# PLT-01-RevE.net
KiCad netlist of a schematic drawn in EAGLE
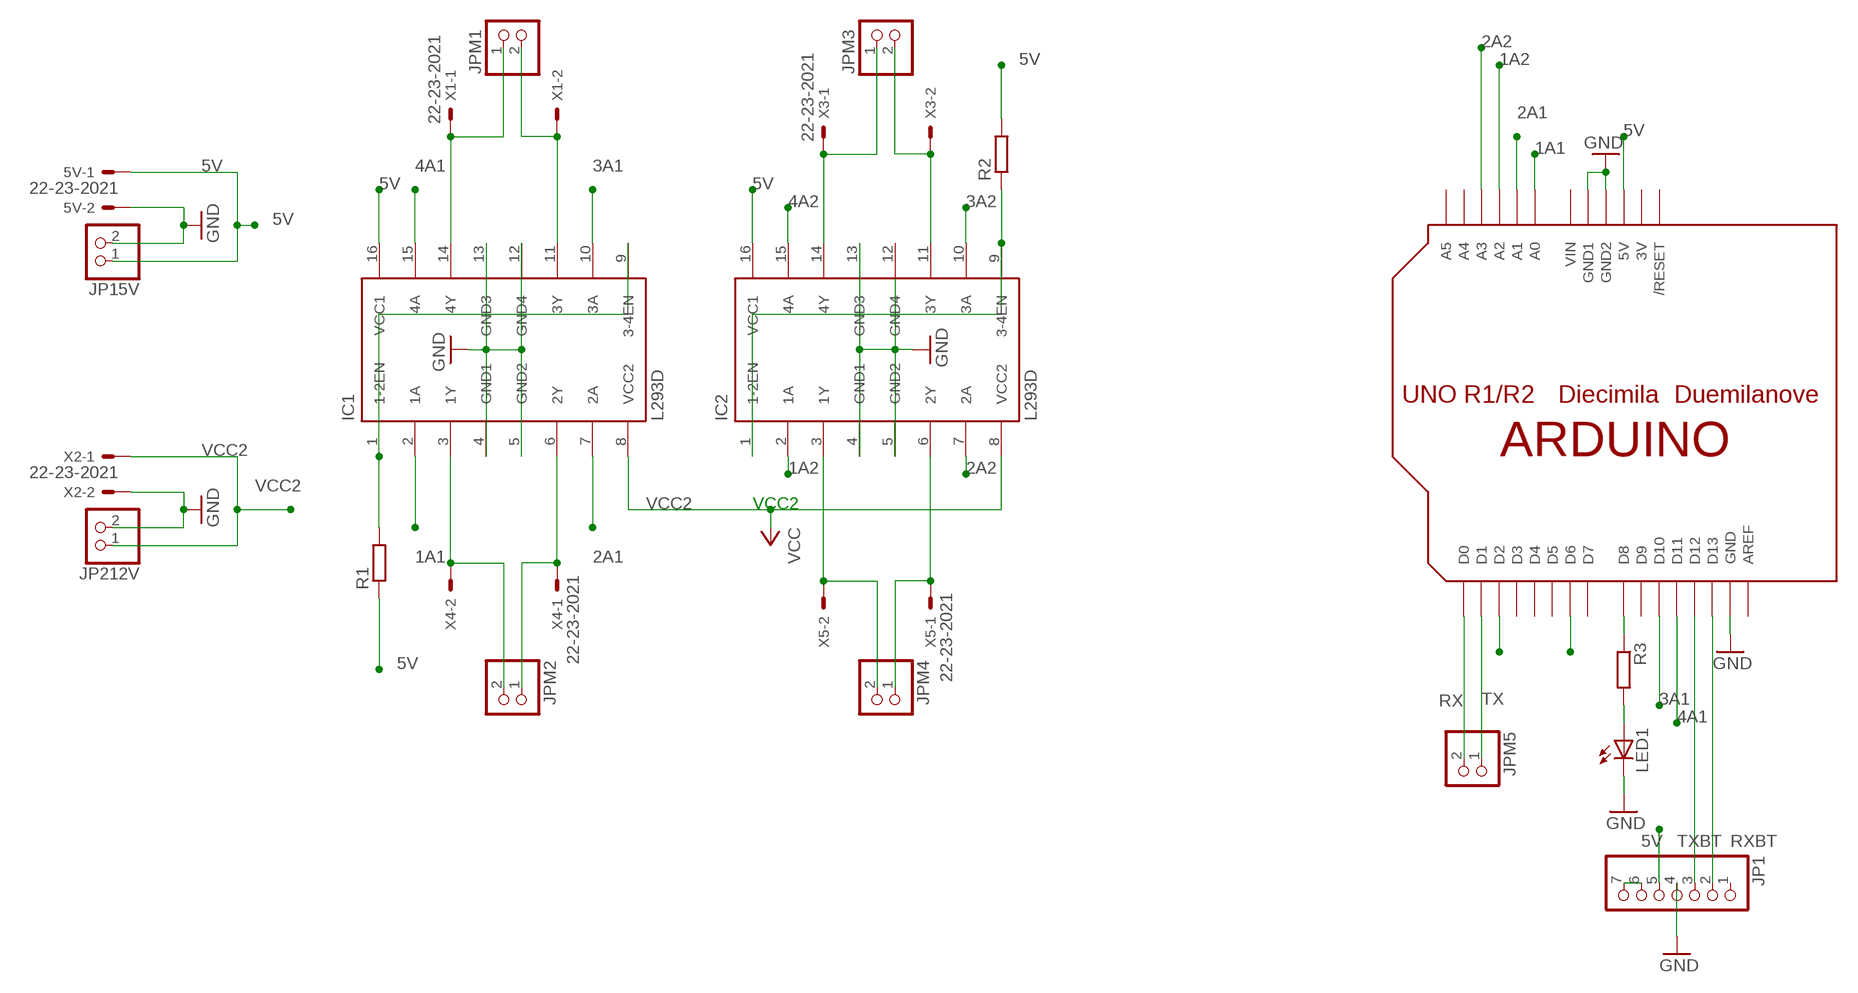
[diagram p0: schematic, sheet 1]

(export (version "E")
  (design (tool "Eeschema 10.0.6"))
  (components
    (comp (ref "5V")
      (value "22-23-2021")
      (footprint "eagle-import:22-23-2021")
      (fields (field (name "MF") "MOLEX"))
      (libsource (lib "eagle-import") (part "22-23-2021"))
    )
    (comp (ref "IC1")
      (value "L293D")
      (footprint "eagle-import:DIL16")
      (libsource (lib "eagle-import") (part "L293D"))
    )
    (comp (ref "IC2")
      (value "L293D")
      (footprint "eagle-import:DIL16")
      (libsource (lib "eagle-import") (part "L293D"))
    )
    (comp (ref "JP1")
      (value "PINHD-1X7")
      (footprint "eagle-import:1X07")
      (libsource (lib "eagle-import") (part "PINHD-1X7"))
    )
    (comp (ref "JP15V")
      (value "PINHD-1X2")
      (footprint "eagle-import:1X02")
      (libsource (lib "eagle-import") (part "PINHD-1X2"))
    )
    (comp (ref "JP212V")
      (value "PINHD-1X2")
      (footprint "eagle-import:1X02")
      (libsource (lib "eagle-import") (part "PINHD-1X2"))
    )
    (comp (ref "JPM1")
      (value "PINHD-1X2")
      (footprint "eagle-import:1X02")
      (libsource (lib "eagle-import") (part "PINHD-1X2"))
    )
    (comp (ref "JPM2")
      (value "PINHD-1X2")
      (footprint "eagle-import:1X02")
      (libsource (lib "eagle-import") (part "PINHD-1X2"))
    )
    (comp (ref "JPM3")
      (value "PINHD-1X2")
      (footprint "eagle-import:1X02")
      (libsource (lib "eagle-import") (part "PINHD-1X2"))
    )
    (comp (ref "JPM4")
      (value "PINHD-1X2")
      (footprint "eagle-import:1X02")
      (libsource (lib "eagle-import") (part "PINHD-1X2"))
    )
    (comp (ref "JPM5")
      (value "PINHD-1X2")
      (footprint "eagle-import:1X02")
      (libsource (lib "eagle-import") (part "PINHD-1X2"))
    )
    (comp (ref "LED1")
      (value "LED5MM")
      (footprint "eagle-import:LED5MM")
      (libsource (lib "eagle-import") (part "LED5MM"))
    )
    (comp (ref "R1")
      (value "R-EU_0207/10")
      (footprint "eagle-import:0207_10")
      (libsource (lib "eagle-import") (part "R-EU_0207/10"))
    )
    (comp (ref "R2")
      (value "R-EU_0207/10")
      (footprint "eagle-import:0207_10")
      (libsource (lib "eagle-import") (part "R-EU_0207/10"))
    )
    (comp (ref "R3")
      (value "R-EU_0207/10")
      (footprint "eagle-import:0207_10")
      (libsource (lib "eagle-import") (part "R-EU_0207/10"))
    )
    (comp (ref "U$1")
      (value "ARDUINOUNO")
      (footprint "eagle-import:ARDUINO")
      (libsource (lib "eagle-import") (part "ARDUINOUNO"))
    )
    (comp (ref "X1")
      (value "22-23-2021")
      (footprint "eagle-import:22-23-2021")
      (fields (field (name "MF") "MOLEX"))
      (libsource (lib "eagle-import") (part "22-23-2021"))
    )
    (comp (ref "X2")
      (value "22-23-2021")
      (footprint "eagle-import:22-23-2021")
      (fields (field (name "MF") "MOLEX"))
      (libsource (lib "eagle-import") (part "22-23-2021"))
    )
    (comp (ref "X3")
      (value "22-23-2021")
      (footprint "eagle-import:22-23-2021")
      (fields (field (name "MF") "MOLEX"))
      (libsource (lib "eagle-import") (part "22-23-2021"))
    )
    (comp (ref "X4")
      (value "22-23-2021")
      (footprint "eagle-import:22-23-2021")
      (fields (field (name "MF") "MOLEX"))
      (libsource (lib "eagle-import") (part "22-23-2021"))
    )
    (comp (ref "X5")
      (value "22-23-2021")
      (footprint "eagle-import:22-23-2021")
      (fields (field (name "MF") "MOLEX"))
      (libsource (lib "eagle-import") (part "22-23-2021"))
    )
  )
  (nets
    (net (code "1") (name "/1A1") (class "Default")
      (node (ref "IC1") (pin "2") (pinfunction "1A_2") (pintype "input"))
      (node (ref "U$1") (pin "A0") (pinfunction "A0_A0") (pintype "bidirectional"))
    )
    (net (code "2") (name "/1A2") (class "Default")
      (node (ref "IC2") (pin "2") (pinfunction "1A_2") (pintype "input"))
      (node (ref "U$1") (pin "A2") (pinfunction "A2_A2") (pintype "bidirectional"))
    )
    (net (code "3") (name "/2A1") (class "Default")
      (node (ref "IC1") (pin "7") (pinfunction "2A_7") (pintype "input"))
      (node (ref "U$1") (pin "A1") (pinfunction "A1_A1") (pintype "bidirectional"))
    )
    (net (code "4") (name "/2A2") (class "Default")
      (node (ref "IC2") (pin "7") (pinfunction "2A_7") (pintype "input"))
      (node (ref "U$1") (pin "A3") (pinfunction "A3_A3") (pintype "bidirectional"))
    )
    (net (code "5") (name "/3A1") (class "Default")
      (node (ref "IC1") (pin "10") (pinfunction "3A_10") (pintype "input"))
      (node (ref "U$1") (pin "D10") (pinfunction "D10_D10") (pintype "bidirectional"))
    )
    (net (code "6") (name "/3A2") (class "Default")
      (node (ref "IC2") (pin "10") (pinfunction "3A_10") (pintype "input"))
      (node (ref "U$1") (pin "D2") (pinfunction "D2_D2") (pintype "bidirectional"))
    )
    (net (code "7") (name "/3V") (class "Default")
      (node (ref "U$1") (pin "3V") (pinfunction "3V_3V") (pintype "power_in"))
    )
    (net (code "8") (name "/4A1") (class "Default")
      (node (ref "IC1") (pin "15") (pinfunction "4A_15") (pintype "input"))
      (node (ref "U$1") (pin "D11") (pinfunction "D11_D11") (pintype "bidirectional"))
    )
    (net (code "9") (name "/4A2") (class "Default")
      (node (ref "IC2") (pin "15") (pinfunction "4A_15") (pintype "input"))
      (node (ref "U$1") (pin "D6") (pinfunction "D6_D6") (pintype "bidirectional"))
    )
    (net (code "10") (name "/5V") (class "Default")
      (node (ref "5V") (pin "1") (pinfunction "S_1") (pintype "passive"))
      (node (ref "IC1") (pin "16") (pinfunction "VCC1_16") (pintype "power_in"))
      (node (ref "IC2") (pin "16") (pinfunction "VCC1_16") (pintype "power_in"))
      (node (ref "JP1") (pin "5") (pinfunction "5_5") (pintype "passive"))
      (node (ref "JP15V") (pin "1") (pinfunction "1_1") (pintype "passive"))
      (node (ref "R1") (pin "1") (pinfunction "1_1") (pintype "passive"))
      (node (ref "R2") (pin "2") (pinfunction "2_2") (pintype "passive"))
      (node (ref "U$1") (pin "5V") (pinfunction "5V_5V") (pintype "power_in"))
    )
    (net (code "11") (name "/GND4") (class "Default")
      (node (ref "IC2") (pin "12") (pinfunction "GND4_12") (pintype "power_in"))
    )
    (net (code "12") (name "/RX") (class "Default")
      (node (ref "JPM5") (pin "2") (pinfunction "2_2") (pintype "passive"))
      (node (ref "U$1") (pin "D0") (pinfunction "D0_D0") (pintype "bidirectional"))
    )
    (net (code "13") (name "/RXBT") (class "Default")
      (node (ref "JP1") (pin "2") (pinfunction "2_2") (pintype "passive"))
      (node (ref "U$1") (pin "D13") (pinfunction "D13_D13") (pintype "bidirectional"))
    )
    (net (code "14") (name "/TX") (class "Default")
      (node (ref "JPM5") (pin "1") (pinfunction "1_1") (pintype "passive"))
      (node (ref "U$1") (pin "D1") (pinfunction "D1_D1") (pintype "bidirectional"))
    )
    (net (code "15") (name "/TXBT") (class "Default")
      (node (ref "JP1") (pin "3") (pinfunction "3_3") (pintype "passive"))
      (node (ref "U$1") (pin "D12") (pinfunction "D12_D12") (pintype "bidirectional"))
    )
    (net (code "16") (name "/VIN") (class "Default")
      (node (ref "U$1") (pin "VIN") (pinfunction "VIN_VIN") (pintype "power_in"))
    )
    (net (code "17") (name "GND") (class "Default")
      (node (ref "5V") (pin "2") (pinfunction "S_2") (pintype "passive"))
      (node (ref "IC1") (pin "12") (pinfunction "GND4_12") (pintype "power_in"))
      (node (ref "IC1") (pin "13") (pinfunction "GND3_13") (pintype "power_in"))
      (node (ref "IC1") (pin "4") (pinfunction "GND1_4") (pintype "power_in"))
      (node (ref "IC1") (pin "5") (pinfunction "GND2_5") (pintype "power_in"))
      (node (ref "IC2") (pin "13") (pinfunction "GND3_13") (pintype "power_in"))
      (node (ref "IC2") (pin "4") (pinfunction "GND1_4") (pintype "power_in"))
      (node (ref "IC2") (pin "5") (pinfunction "GND2_5") (pintype "power_in"))
      (node (ref "JP1") (pin "4") (pinfunction "4_4") (pintype "passive"))
      (node (ref "JP15V") (pin "2") (pinfunction "2_2") (pintype "passive"))
      (node (ref "JP212V") (pin "2") (pinfunction "2_2") (pintype "passive"))
      (node (ref "LED1") (pin "K") (pinfunction "C_K") (pintype "passive"))
      (node (ref "U$1") (pin "GND") (pinfunction "GND_GND") (pintype "power_in"))
      (node (ref "U$1") (pin "GND1") (pinfunction "GND1_GND1") (pintype "power_in"))
      (node (ref "U$1") (pin "GND2") (pinfunction "GND2_GND2") (pintype "power_in"))
      (node (ref "X2") (pin "2") (pinfunction "S_2") (pintype "passive"))
    )
    (net (code "18") (name "Net-(IC1-1-2EN)") (class "Default")
      (node (ref "IC1") (pin "1") (pinfunction "1-2EN_1") (pintype "input"))
      (node (ref "IC1") (pin "9") (pinfunction "3-4EN_9") (pintype "input"))
      (node (ref "R1") (pin "2") (pinfunction "2_2") (pintype "passive"))
    )
    (net (code "19") (name "Net-(IC1-1Y)") (class "Default")
      (node (ref "IC1") (pin "3") (pinfunction "1Y_3") (pintype "output"))
      (node (ref "JPM2") (pin "2") (pinfunction "2_2") (pintype "passive"))
      (node (ref "X4") (pin "2") (pinfunction "S_2") (pintype "passive"))
    )
    (net (code "20") (name "Net-(IC1-2Y)") (class "Default")
      (node (ref "IC1") (pin "6") (pinfunction "2Y_6") (pintype "output"))
      (node (ref "JPM2") (pin "1") (pinfunction "1_1") (pintype "passive"))
      (node (ref "X4") (pin "1") (pinfunction "S_1") (pintype "passive"))
    )
    (net (code "21") (name "Net-(IC1-3Y)") (class "Default")
      (node (ref "IC1") (pin "11") (pinfunction "3Y_11") (pintype "output"))
      (node (ref "JPM1") (pin "2") (pinfunction "2_2") (pintype "passive"))
      (node (ref "X1") (pin "2") (pinfunction "S_2") (pintype "passive"))
    )
    (net (code "22") (name "Net-(IC1-4Y)") (class "Default")
      (node (ref "IC1") (pin "14") (pinfunction "4Y_14") (pintype "output"))
      (node (ref "JPM1") (pin "1") (pinfunction "1_1") (pintype "passive"))
      (node (ref "X1") (pin "1") (pinfunction "S_1") (pintype "passive"))
    )
    (net (code "23") (name "Net-(IC2-1-2EN)") (class "Default")
      (node (ref "IC2") (pin "1") (pinfunction "1-2EN_1") (pintype "input"))
      (node (ref "IC2") (pin "9") (pinfunction "3-4EN_9") (pintype "input"))
      (node (ref "R2") (pin "1") (pinfunction "1_1") (pintype "passive"))
    )
    (net (code "24") (name "Net-(IC2-1Y)") (class "Default")
      (node (ref "IC2") (pin "3") (pinfunction "1Y_3") (pintype "output"))
      (node (ref "JPM4") (pin "2") (pinfunction "2_2") (pintype "passive"))
      (node (ref "X5") (pin "2") (pinfunction "S_2") (pintype "passive"))
    )
    (net (code "25") (name "Net-(IC2-2Y)") (class "Default")
      (node (ref "IC2") (pin "6") (pinfunction "2Y_6") (pintype "output"))
      (node (ref "JPM4") (pin "1") (pinfunction "1_1") (pintype "passive"))
      (node (ref "X5") (pin "1") (pinfunction "S_1") (pintype "passive"))
    )
    (net (code "26") (name "Net-(IC2-3Y)") (class "Default")
      (node (ref "IC2") (pin "11") (pinfunction "3Y_11") (pintype "output"))
      (node (ref "JPM3") (pin "2") (pinfunction "2_2") (pintype "passive"))
      (node (ref "X3") (pin "2") (pinfunction "S_2") (pintype "passive"))
    )
    (net (code "27") (name "Net-(IC2-4Y)") (class "Default")
      (node (ref "IC2") (pin "14") (pinfunction "4Y_14") (pintype "output"))
      (node (ref "JPM3") (pin "1") (pinfunction "1_1") (pintype "passive"))
      (node (ref "X3") (pin "1") (pinfunction "S_1") (pintype "passive"))
    )
    (net (code "28") (name "Net-(JP1-Pad6)") (class "Default")
      (node (ref "JP1") (pin "6") (pinfunction "6_6") (pintype "passive"))
      (node (ref "JP1") (pin "7") (pinfunction "7_7") (pintype "passive"))
    )
    (net (code "29") (name "Net-(LED1-PadA)") (class "Default")
      (node (ref "LED1") (pin "A") (pinfunction "A_A") (pintype "passive"))
      (node (ref "R3") (pin "2") (pinfunction "2_2") (pintype "passive"))
    )
    (net (code "30") (name "Net-(R3-Pad1)") (class "Default")
      (node (ref "R3") (pin "1") (pinfunction "1_1") (pintype "passive"))
      (node (ref "U$1") (pin "D8") (pinfunction "D8_D8") (pintype "bidirectional"))
    )
    (net (code "31") (name "VCC") (class "Default")
      (node (ref "IC1") (pin "8") (pinfunction "VCC2_8") (pintype "power_in"))
      (node (ref "IC2") (pin "8") (pinfunction "VCC2_8") (pintype "power_in"))
      (node (ref "JP212V") (pin "1") (pinfunction "1_1") (pintype "passive"))
      (node (ref "X2") (pin "1") (pinfunction "S_1") (pintype "passive"))
    )
    (net (code "32") (name "unconnected-(JP1-Pad1)") (class "Default")
      (node (ref "JP1") (pin "1") (pinfunction "1_1") (pintype "passive"))
    )
    (net (code "33") (name "unconnected-(U$1-PadA4)") (class "Default")
      (node (ref "U$1") (pin "A4") (pinfunction "A4_A4") (pintype "bidirectional"))
    )
    (net (code "34") (name "unconnected-(U$1-PadA5)") (class "Default")
      (node (ref "U$1") (pin "A5") (pinfunction "A5_A5") (pintype "bidirectional"))
    )
    (net (code "35") (name "unconnected-(U$1-PadAREF)") (class "Default")
      (node (ref "U$1") (pin "AREF") (pinfunction "AREF_AREF") (pintype "bidirectional"))
    )
    (net (code "36") (name "unconnected-(U$1-PadD3)") (class "Default")
      (node (ref "U$1") (pin "D3") (pinfunction "D3_D3") (pintype "bidirectional"))
    )
    (net (code "37") (name "unconnected-(U$1-PadD4)") (class "Default")
      (node (ref "U$1") (pin "D4") (pinfunction "D4_D4") (pintype "bidirectional"))
    )
    (net (code "38") (name "unconnected-(U$1-PadD5)") (class "Default")
      (node (ref "U$1") (pin "D5") (pinfunction "D5_D5") (pintype "bidirectional"))
    )
    (net (code "39") (name "unconnected-(U$1-PadD7)") (class "Default")
      (node (ref "U$1") (pin "D7") (pinfunction "D7_D7") (pintype "bidirectional"))
    )
    (net (code "40") (name "unconnected-(U$1-PadD9)") (class "Default")
      (node (ref "U$1") (pin "D9") (pinfunction "D9_D9") (pintype "bidirectional"))
    )
    (net (code "41") (name "unconnected-(U$1-{slash}RESET-PadRESET)") (class "Default")
      (node (ref "U$1") (pin "RESET") (pinfunction "/RESET_RESET") (pintype "bidirectional"))
    )
  )
)
